# schV2.net
KiCad netlist of a schematic drawn in EAGLE
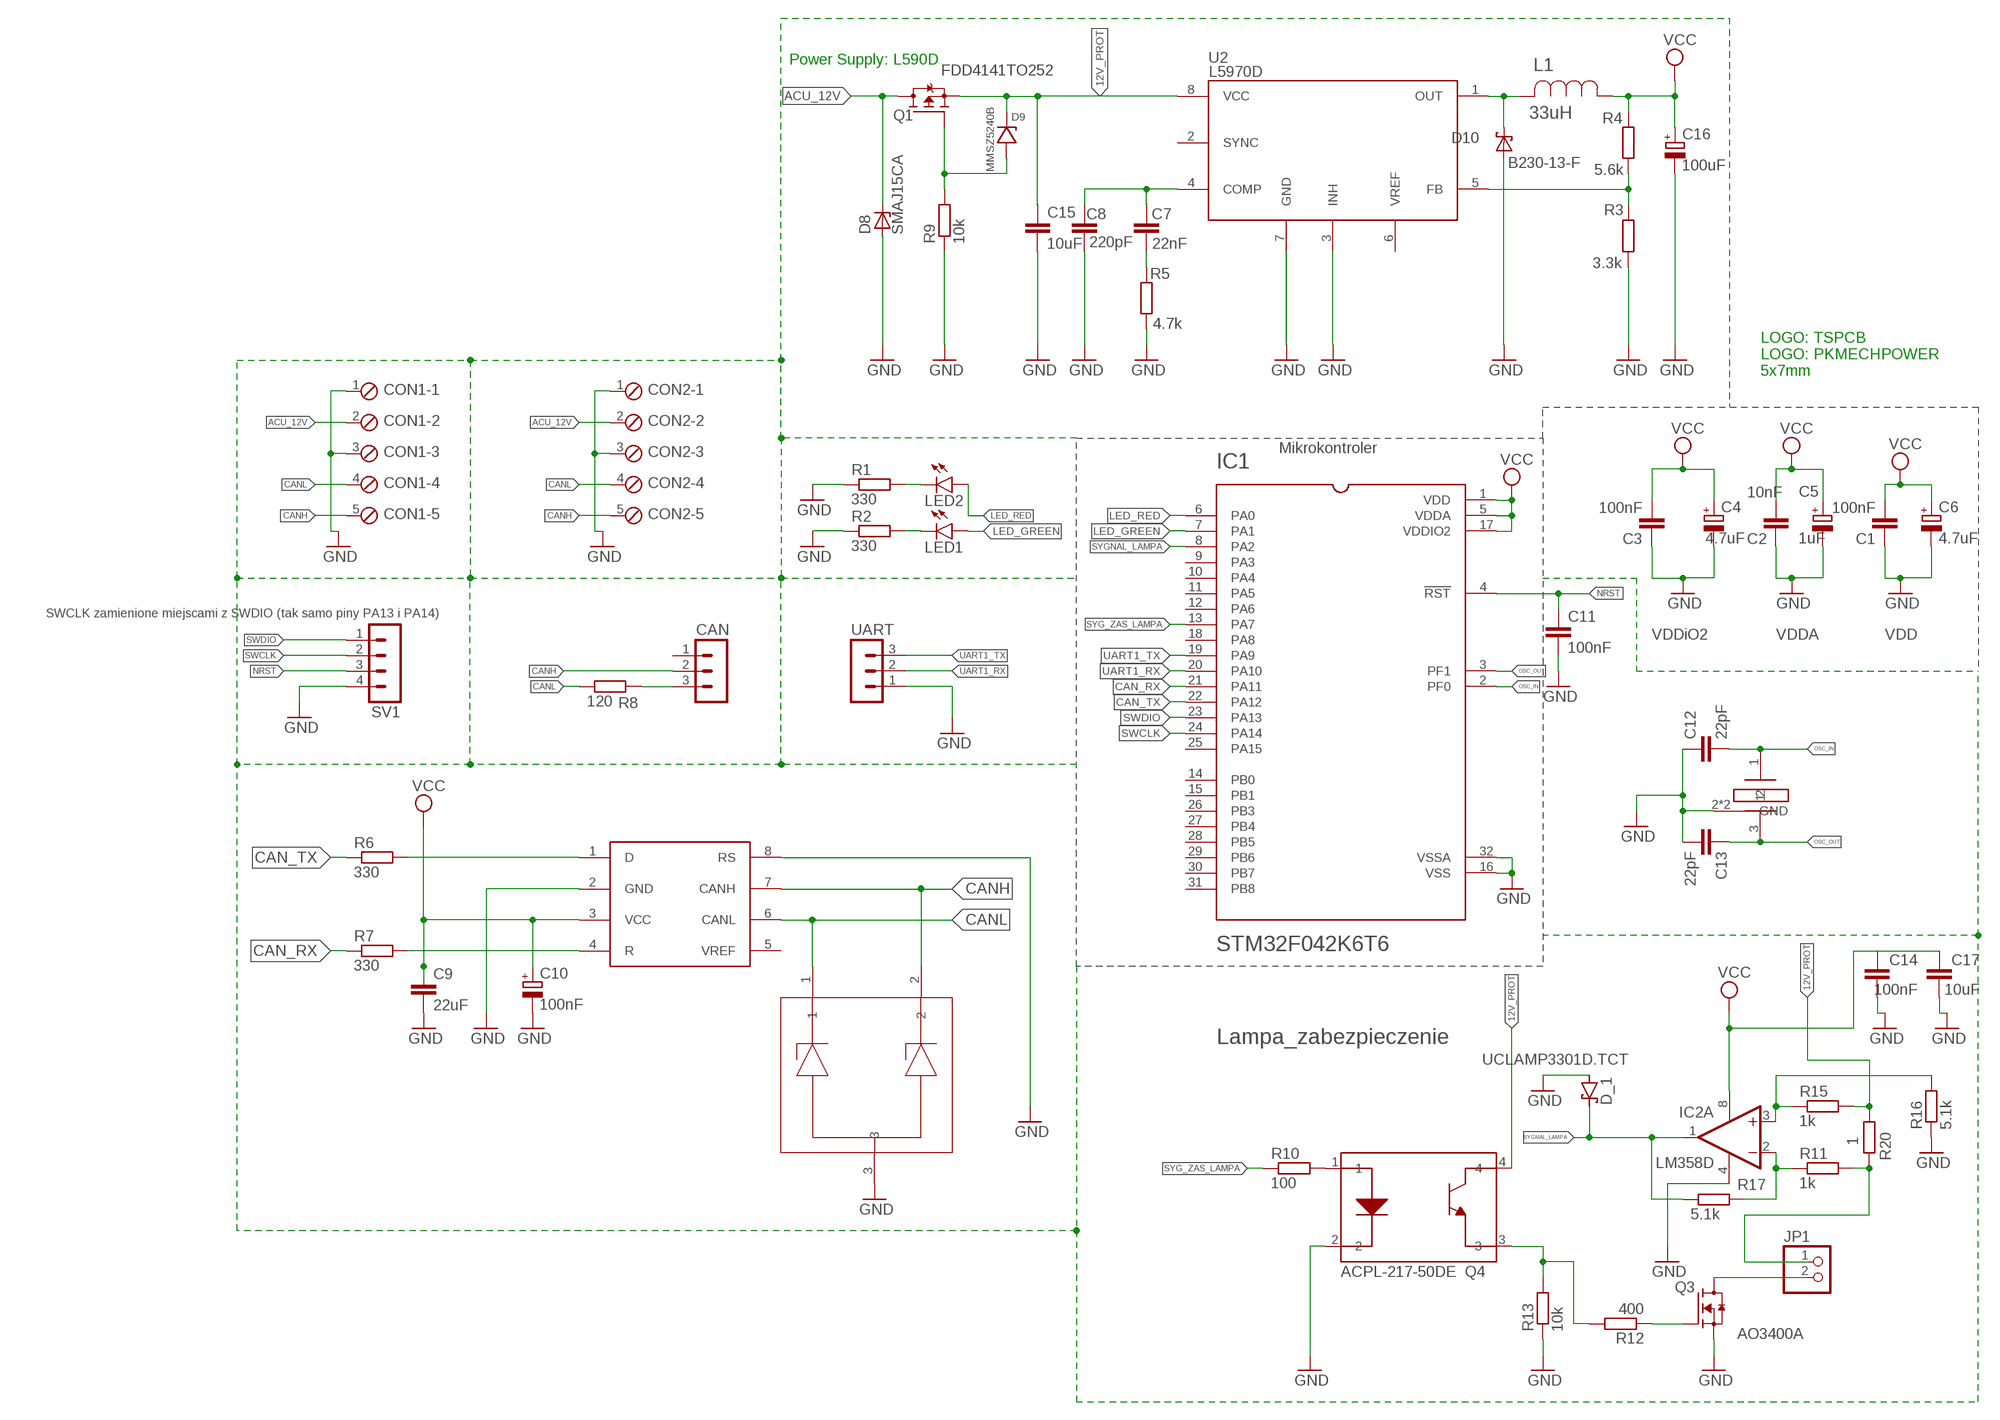
[diagram p0: schematic, sheet 1]

(export (version "E")
  (design (tool "Eeschema 10.0.6"))
  (components
    (comp (ref "C1")
      (value "100nF")
      (footprint "eagle-import:C0805")
      (libsource (lib "eagle-import") (part "C-EUC0805"))
    )
    (comp (ref "C2")
      (value "10nF")
      (footprint "eagle-import:C0805")
      (libsource (lib "eagle-import") (part "C-EUC0805"))
    )
    (comp (ref "C3")
      (value "100nF")
      (footprint "eagle-import:C0805")
      (libsource (lib "eagle-import") (part "C-EUC0805"))
    )
    (comp (ref "C4")
      (value "4.7uF")
      (footprint "eagle-import:SMC_C")
      (libsource (lib "eagle-import") (part "CPOL-EUSMCC"))
    )
    (comp (ref "C5")
      (value "1uF")
      (footprint "eagle-import:SMC_C")
      (libsource (lib "eagle-import") (part "CPOL-EUSMCC"))
    )
    (comp (ref "C6")
      (value "4.7uF")
      (footprint "eagle-import:SMC_C")
      (libsource (lib "eagle-import") (part "CPOL-EUSMCC"))
    )
    (comp (ref "C7")
      (value "22nF")
      (footprint "eagle-import:C0805")
      (libsource (lib "eagle-import") (part "C-EUC0805"))
    )
    (comp (ref "C8")
      (value "220pF")
      (footprint "eagle-import:C0805")
      (libsource (lib "eagle-import") (part "C-EUC0805"))
    )
    (comp (ref "C9")
      (value "22uF")
      (footprint "eagle-import:C0805")
      (libsource (lib "eagle-import") (part "C-EUC0805"))
    )
    (comp (ref "C10")
      (value "100nF")
      (footprint "eagle-import:SMC_C")
      (libsource (lib "eagle-import") (part "CPOL-EUSMCC"))
    )
    (comp (ref "C11")
      (value "100nF")
      (footprint "eagle-import:C0805")
      (libsource (lib "eagle-import") (part "C-EUC0805"))
    )
    (comp (ref "C12")
      (value "22pF")
      (footprint "eagle-import:C0805")
      (libsource (lib "eagle-import") (part "C-EUC0805"))
    )
    (comp (ref "C13")
      (value "22pF")
      (footprint "eagle-import:C0805")
      (libsource (lib "eagle-import") (part "C-EUC0805"))
    )
    (comp (ref "C14")
      (value "100nF")
      (footprint "eagle-import:C0805")
      (libsource (lib "eagle-import") (part "C-EUC0805"))
    )
    (comp (ref "C15")
      (value "10uF")
      (footprint "eagle-import:C1210")
      (libsource (lib "eagle-import") (part "C-EUC1210"))
    )
    (comp (ref "C16")
      (value "100uF")
      (footprint "eagle-import:SMC_D")
      (libsource (lib "eagle-import") (part "CPOL-EUSMCD"))
    )
    (comp (ref "C17")
      (value "10uF")
      (footprint "eagle-import:C0805")
      (libsource (lib "eagle-import") (part "C-EUC0805"))
    )
    (comp (ref "CAN")
      (value "MA03-1")
      (footprint "eagle-import:MA03-1")
      (libsource (lib "eagle-import") (part "MA03-1"))
    )
    (comp (ref "CON1")
      (value "MPT5")
      (footprint "eagle-import:5POL254")
      (libsource (lib "eagle-import") (part "MPT5"))
    )
    (comp (ref "CON2")
      (value "MPT5")
      (footprint "eagle-import:5POL254")
      (libsource (lib "eagle-import") (part "MPT5"))
    )
    (comp (ref "D8")
      (value "SMAJ15CA")
      (footprint "eagle-import:SMA")
      (fields (field (name "MF") "Nexperia USA") (field (name "MP") "PESD5V0X1UB"))
      (libsource (lib "eagle-import") (part "SMAJ15CA"))
    )
    (comp (ref "D9")
      (value "MMSZ5240B")
      (footprint "eagle-import:SOD123")
      (libsource (lib "eagle-import") (part "ZENER_01"))
    )
    (comp (ref "D10")
      (value "B230-13-F")
      (footprint "eagle-import:SMB")
      (libsource (lib "eagle-import") (part "B230-13-F"))
    )
    (comp (ref "D_1")
      (value "UCLAMP3301D.TCT")
      (footprint "eagle-import:SOD323")
      (libsource (lib "eagle-import") (part "UCLAMP3301D.TCT"))
    )
    (comp (ref "IC1")
      (value "STM32F042K6T6")
      (footprint "eagle-import:QFP80P900X900X160-32N")
      (fields (field (name "MF") "STMicroelectronics"))
      (libsource (lib "eagle-import") (part "STM32F042K6T6"))
    )
    (comp (ref "IC2")
      (value "LM358D")
      (footprint "eagle-import:SO08")
      (libsource (lib "eagle-import") (part "LM358D"))
    )
    (comp (ref "JP1")
      (value "PINHD-1X2")
      (footprint "eagle-import:1X02")
      (libsource (lib "eagle-import") (part "PINHD-1X2"))
    )
    (comp (ref "L1")
      (value "33uH")
      (footprint "eagle-import:INDM125125X600N")
      (fields (field (name "MF") "Coilcraft") (field (name "MP") "DR125-680-R"))
      (libsource (lib "eagle-import") (part "DR125-680-R"))
    )
    (comp (ref "LED1")
      (value "LEDCHIP-LED0805")
      (footprint "eagle-import:CHIP-LED0805")
      (libsource (lib "eagle-import") (part "LEDCHIP-LED0805"))
    )
    (comp (ref "LED2")
      (value "LEDCHIP-LED0805")
      (footprint "eagle-import:CHIP-LED0805")
      (libsource (lib "eagle-import") (part "LEDCHIP-LED0805"))
    )
    (comp (ref "Q1")
      (value "FDD4141TO252")
      (footprint "eagle-import:TO252")
      (libsource (lib "eagle-import") (part "FDD4141TO252"))
    )
    (comp (ref "Q3")
      (value "AO3400A")
      (footprint "eagle-import:SOT95P280X125-3N")
      (fields (field (name "MF") "Alpha &"))
      (libsource (lib "eagle-import") (part "AO3400A"))
    )
    (comp (ref "Q4")
      (value "ACPL-217-50DE")
      (footprint "eagle-import:SOIC127P700X220-4N")
      (fields (field (name "MF") "Broadcom / Avago"))
      (libsource (lib "eagle-import") (part "ACPL-217-50DE"))
    )
    (comp (ref "R1")
      (value "330")
      (footprint "eagle-import:R0805")
      (libsource (lib "eagle-import") (part "R-EU_R0805"))
    )
    (comp (ref "R2")
      (value "330")
      (footprint "eagle-import:R0805")
      (libsource (lib "eagle-import") (part "R-EU_R0805"))
    )
    (comp (ref "R3")
      (value "3.3k")
      (footprint "eagle-import:R0805")
      (libsource (lib "eagle-import") (part "R-EU_R0805"))
    )
    (comp (ref "R4")
      (value "5.6k")
      (footprint "eagle-import:R0805")
      (libsource (lib "eagle-import") (part "R-EU_R0805"))
    )
    (comp (ref "R5")
      (value "4.7k")
      (footprint "eagle-import:R0805")
      (libsource (lib "eagle-import") (part "R-EU_R0805"))
    )
    (comp (ref "R6")
      (value "330")
      (footprint "eagle-import:M0805")
      (libsource (lib "eagle-import") (part "R-EU_M0805"))
    )
    (comp (ref "R7")
      (value "330")
      (footprint "eagle-import:M0805")
      (libsource (lib "eagle-import") (part "R-EU_M0805"))
    )
    (comp (ref "R8")
      (value "120")
      (footprint "eagle-import:M0805")
      (libsource (lib "eagle-import") (part "R-EU_M0805"))
    )
    (comp (ref "R9")
      (value "10k")
      (footprint "eagle-import:R0805")
      (libsource (lib "eagle-import") (part "R-EU_R0805"))
    )
    (comp (ref "R10")
      (value "100")
      (footprint "eagle-import:M0805")
      (libsource (lib "eagle-import") (part "R-EU_M0805"))
    )
    (comp (ref "R11")
      (value "1k")
      (footprint "eagle-import:M0805")
      (libsource (lib "eagle-import") (part "R-EU_M0805"))
    )
    (comp (ref "R12")
      (value "400")
      (footprint "eagle-import:M0805")
      (libsource (lib "eagle-import") (part "R-EU_M0805"))
    )
    (comp (ref "R13")
      (value "10k")
      (footprint "eagle-import:M0805")
      (libsource (lib "eagle-import") (part "R-EU_M0805"))
    )
    (comp (ref "R15")
      (value "1k")
      (footprint "eagle-import:M0805")
      (libsource (lib "eagle-import") (part "R-EU_M0805"))
    )
    (comp (ref "R16")
      (value "5.1k")
      (footprint "eagle-import:M0805")
      (libsource (lib "eagle-import") (part "R-EU_M0805"))
    )
    (comp (ref "R17")
      (value "5.1k")
      (footprint "eagle-import:M0805")
      (libsource (lib "eagle-import") (part "R-EU_M0805"))
    )
    (comp (ref "R20")
      (value "1")
      (footprint "eagle-import:R2512")
      (libsource (lib "eagle-import") (part "R-EU_R2512"))
    )
    (comp (ref "SV1")
      (value "MA04-1")
      (footprint "eagle-import:MA04-1")
      (libsource (lib "eagle-import") (part "MA04-1"))
    )
    (comp (ref "U$1")
      (value "SN65HVD")
      (footprint "eagle-import:SO8")
      (libsource (lib "eagle-import") (part "SN65HVD"))
    )
    (comp (ref "U$2")
      (value "PESD3V3S2UT_")
      (footprint "eagle-import:SOT95P230X110-3N")
      (libsource (lib "eagle-import") (part "PESD3V3S2UT_"))
    )
    (comp (ref "U2")
      (value "L5970D")
      (footprint "eagle-import:SO-8")
      (fields (field (name "MF") "STMicroelectronics"))
      (libsource (lib "eagle-import") (part "L5970D"))
    )
    (comp (ref "UART")
      (value "MA03-1")
      (footprint "eagle-import:MA03-1")
      (libsource (lib "eagle-import") (part "MA03-1"))
    )
    (comp (ref "XTAL1")
      (value "CRYSTAL_SMDXT-324")
      (footprint "eagle-import:XT-324")
      (libsource (lib "eagle-import") (part "CRYSTAL_SMDXT-324"))
    )
  )
  (nets
    (net (code "1") (name "12V_PROT") (class "Default")
      (node (ref "C15") (pin "1") (pinfunction "1_1") (pintype "passive"))
      (node (ref "D9") (pin "1") (pinfunction "1_1") (pintype "bidirectional"))
      (node (ref "Q1") (pin "2") (pinfunction "S_2") (pintype "passive"))
      (node (ref "Q4") (pin "4") (pinfunction "4_4") (pintype "passive"))
      (node (ref "R15") (pin "2") (pinfunction "2_2") (pintype "passive"))
      (node (ref "R20") (pin "2") (pinfunction "2_2") (pintype "passive"))
      (node (ref "U2") (pin "8") (pinfunction "VCC_8") (pintype "bidirectional"))
    )
    (net (code "2") (name "ACU_12V") (class "Default")
      (node (ref "CON1") (pin "2") (pinfunction "1_2") (pintype "passive"))
      (node (ref "CON2") (pin "2") (pinfunction "1_2") (pintype "passive"))
      (node (ref "D8") (pin "1") (pinfunction "K_1") (pintype "passive"))
      (node (ref "Q1") (pin "3") (pinfunction "D_3") (pintype "passive"))
    )
    (net (code "3") (name "CANH") (class "Default")
      (node (ref "CAN") (pin "2") (pinfunction "2_2") (pintype "passive"))
      (node (ref "CON1") (pin "5") (pinfunction "1_5") (pintype "passive"))
      (node (ref "CON2") (pin "5") (pinfunction "1_5") (pintype "passive"))
      (node (ref "U$1") (pin "7") (pinfunction "CANH_7") (pintype "bidirectional"))
      (node (ref "U$2") (pin "2") (pinfunction "2_2") (pintype "bidirectional"))
    )
    (net (code "4") (name "CANL") (class "Default")
      (node (ref "CON1") (pin "4") (pinfunction "1_4") (pintype "passive"))
      (node (ref "CON2") (pin "4") (pinfunction "1_4") (pintype "passive"))
      (node (ref "R8") (pin "1") (pinfunction "1_1") (pintype "passive"))
      (node (ref "U$1") (pin "6") (pinfunction "CANL_6") (pintype "bidirectional"))
      (node (ref "U$2") (pin "1") (pinfunction "1_1") (pintype "bidirectional"))
    )
    (net (code "5") (name "CAN_RX") (class "Default")
      (node (ref "IC1") (pin "21") (pinfunction "PA11_21") (pintype "bidirectional"))
      (node (ref "R7") (pin "1") (pinfunction "1_1") (pintype "passive"))
    )
    (net (code "6") (name "CAN_TX") (class "Default")
      (node (ref "IC1") (pin "22") (pinfunction "PA12_22") (pintype "bidirectional"))
      (node (ref "R6") (pin "1") (pinfunction "1_1") (pintype "passive"))
    )
    (net (code "7") (name "GND") (class "Default")
      (node (ref "C1") (pin "1") (pinfunction "1_1") (pintype "passive"))
      (node (ref "C10") (pin "-") (pinfunction "-_-") (pintype "passive"))
      (node (ref "C11") (pin "2") (pinfunction "2_2") (pintype "passive"))
      (node (ref "C12") (pin "1") (pinfunction "1_1") (pintype "passive"))
      (node (ref "C13") (pin "2") (pinfunction "2_2") (pintype "passive"))
      (node (ref "C14") (pin "1") (pinfunction "1_1") (pintype "passive"))
      (node (ref "C15") (pin "2") (pinfunction "2_2") (pintype "passive"))
      (node (ref "C16") (pin "-") (pinfunction "-_-") (pintype "passive"))
      (node (ref "C17") (pin "1") (pinfunction "1_1") (pintype "passive"))
      (node (ref "C2") (pin "1") (pinfunction "1_1") (pintype "passive"))
      (node (ref "C3") (pin "1") (pinfunction "1_1") (pintype "passive"))
      (node (ref "C4") (pin "-") (pinfunction "-_-") (pintype "passive"))
      (node (ref "C5") (pin "-") (pinfunction "-_-") (pintype "passive"))
      (node (ref "C6") (pin "-") (pinfunction "-_-") (pintype "passive"))
      (node (ref "C8") (pin "1") (pinfunction "1_1") (pintype "passive"))
      (node (ref "C9") (pin "2") (pinfunction "2_2") (pintype "passive"))
      (node (ref "CON1") (pin "1") (pinfunction "1_1") (pintype "passive"))
      (node (ref "CON1") (pin "3") (pinfunction "1_3") (pintype "passive"))
      (node (ref "CON2") (pin "1") (pinfunction "1_1") (pintype "passive"))
      (node (ref "CON2") (pin "3") (pinfunction "1_3") (pintype "passive"))
      (node (ref "D10") (pin "2") (pinfunction "A_2") (pintype "passive"))
      (node (ref "D8") (pin "2") (pinfunction "A_2") (pintype "passive"))
      (node (ref "D_1") (pin "1") (pinfunction "A_1") (pintype "passive"))
      (node (ref "IC1") (pin "16") (pinfunction "VSS_16") (pintype "passive"))
      (node (ref "IC1") (pin "32") (pinfunction "VSSA_32") (pintype "passive"))
      (node (ref "IC2") (pin "4") (pinfunction "V-_4") (pintype "power_in"))
      (node (ref "Q3") (pin "2") (pinfunction "S_2") (pintype "passive"))
      (node (ref "Q4") (pin "2") (pinfunction "2_2") (pintype "passive"))
      (node (ref "R1") (pin "1") (pinfunction "1_1") (pintype "passive"))
      (node (ref "R13") (pin "1") (pinfunction "1_1") (pintype "passive"))
      (node (ref "R16") (pin "1") (pinfunction "1_1") (pintype "passive"))
      (node (ref "R2") (pin "1") (pinfunction "1_1") (pintype "passive"))
      (node (ref "R3") (pin "1") (pinfunction "1_1") (pintype "passive"))
      (node (ref "R5") (pin "1") (pinfunction "1_1") (pintype "passive"))
      (node (ref "R9") (pin "1") (pinfunction "1_1") (pintype "passive"))
      (node (ref "SV1") (pin "4") (pinfunction "4_4") (pintype "passive"))
      (node (ref "U$1") (pin "2") (pinfunction "GND_2") (pintype "bidirectional"))
      (node (ref "U$1") (pin "8") (pinfunction "RS_8") (pintype "bidirectional"))
      (node (ref "U$2") (pin "3") (pinfunction "3_3") (pintype "bidirectional"))
      (node (ref "U2") (pin "3") (pinfunction "INH_3") (pintype "bidirectional"))
      (node (ref "U2") (pin "7") (pinfunction "GND_7") (pintype "bidirectional"))
      (node (ref "UART") (pin "1") (pinfunction "1_1") (pintype "passive"))
      (node (ref "XTAL1") (pin "2") (pinfunction "GND_2") (pintype "bidirectional"))
      (node (ref "XTAL1") (pin "4") (pinfunction "GND_4") (pintype "bidirectional"))
    )
    (net (code "8") (name "LED_GREEN") (class "Default")
      (node (ref "IC1") (pin "7") (pinfunction "PA1_7") (pintype "bidirectional"))
      (node (ref "LED1") (pin "A") (pinfunction "A_A") (pintype "passive"))
    )
    (net (code "9") (name "LED_RED") (class "Default")
      (node (ref "IC1") (pin "6") (pinfunction "PA0_6") (pintype "bidirectional"))
      (node (ref "LED2") (pin "A") (pinfunction "A_A") (pintype "passive"))
    )
    (net (code "10") (name "NRST") (class "Default")
      (node (ref "C11") (pin "1") (pinfunction "1_1") (pintype "passive"))
      (node (ref "IC1") (pin "4") (pinfunction "~{RST}_4") (pintype "input"))
      (node (ref "SV1") (pin "3") (pinfunction "3_3") (pintype "passive"))
    )
    (net (code "11") (name "Net-(C7-Pad1)") (class "Default")
      (node (ref "C7") (pin "1") (pinfunction "1_1") (pintype "passive"))
      (node (ref "R5") (pin "2") (pinfunction "2_2") (pintype "passive"))
    )
    (net (code "12") (name "Net-(CAN-Pad3)") (class "Default")
      (node (ref "CAN") (pin "3") (pinfunction "3_3") (pintype "passive"))
      (node (ref "R8") (pin "2") (pinfunction "2_2") (pintype "passive"))
    )
    (net (code "13") (name "Net-(D10-K)") (class "Default")
      (node (ref "D10") (pin "1") (pinfunction "K_1") (pintype "passive"))
      (node (ref "L1") (pin "2") (pinfunction "2_2") (pintype "passive"))
      (node (ref "U2") (pin "1") (pinfunction "OUT_1") (pintype "bidirectional"))
    )
    (net (code "14") (name "Net-(IC2A-+IN)") (class "Default")
      (node (ref "IC2") (pin "3") (pinfunction "+IN_3") (pintype "input"))
      (node (ref "R15") (pin "1") (pinfunction "1_1") (pintype "passive"))
      (node (ref "R16") (pin "2") (pinfunction "2_2") (pintype "passive"))
    )
    (net (code "15") (name "Net-(IC2A--IN)") (class "Default")
      (node (ref "IC2") (pin "2") (pinfunction "-IN_2") (pintype "input"))
      (node (ref "R11") (pin "1") (pinfunction "1_1") (pintype "passive"))
      (node (ref "R17") (pin "2") (pinfunction "2_2") (pintype "passive"))
    )
    (net (code "16") (name "Net-(JP1-Pad1)") (class "Default")
      (node (ref "JP1") (pin "1") (pinfunction "1_1") (pintype "passive"))
      (node (ref "R11") (pin "2") (pinfunction "2_2") (pintype "passive"))
      (node (ref "R20") (pin "1") (pinfunction "1_1") (pintype "passive"))
    )
    (net (code "17") (name "Net-(LED1-PadC)") (class "Default")
      (node (ref "LED1") (pin "C") (pinfunction "C_C") (pintype "passive"))
      (node (ref "R2") (pin "2") (pinfunction "2_2") (pintype "passive"))
    )
    (net (code "18") (name "Net-(LED2-PadC)") (class "Default")
      (node (ref "LED2") (pin "C") (pinfunction "C_C") (pintype "passive"))
      (node (ref "R1") (pin "2") (pinfunction "2_2") (pintype "passive"))
    )
    (net (code "19") (name "Net-(Q1-G)") (class "Default")
      (node (ref "D9") (pin "2") (pinfunction "2_2") (pintype "bidirectional"))
      (node (ref "Q1") (pin "1") (pinfunction "G_1") (pintype "passive"))
      (node (ref "R9") (pin "2") (pinfunction "2_2") (pintype "passive"))
    )
    (net (code "20") (name "Net-(Q3-D)") (class "Default")
      (node (ref "JP1") (pin "2") (pinfunction "2_2") (pintype "passive"))
      (node (ref "Q3") (pin "3") (pinfunction "D_3") (pintype "passive"))
    )
    (net (code "21") (name "Net-(Q3-G)") (class "Default")
      (node (ref "Q3") (pin "1") (pinfunction "G_1") (pintype "passive"))
      (node (ref "R12") (pin "1") (pinfunction "1_1") (pintype "passive"))
    )
    (net (code "22") (name "Net-(Q4-Pad1)") (class "Default")
      (node (ref "Q4") (pin "1") (pinfunction "1_1") (pintype "passive"))
      (node (ref "R10") (pin "2") (pinfunction "2_2") (pintype "passive"))
    )
    (net (code "23") (name "Net-(Q4-Pad3)") (class "Default")
      (node (ref "Q4") (pin "3") (pinfunction "3_3") (pintype "passive"))
      (node (ref "R12") (pin "2") (pinfunction "2_2") (pintype "passive"))
      (node (ref "R13") (pin "2") (pinfunction "2_2") (pintype "passive"))
    )
    (net (code "24") (name "Net-(U$1-D)") (class "Default")
      (node (ref "R6") (pin "2") (pinfunction "2_2") (pintype "passive"))
      (node (ref "U$1") (pin "1") (pinfunction "D_1") (pintype "bidirectional"))
    )
    (net (code "25") (name "Net-(U$1-R)") (class "Default")
      (node (ref "R7") (pin "2") (pinfunction "2_2") (pintype "passive"))
      (node (ref "U$1") (pin "4") (pinfunction "R_4") (pintype "bidirectional"))
    )
    (net (code "26") (name "Net-(U2-COMP)") (class "Default")
      (node (ref "C7") (pin "2") (pinfunction "2_2") (pintype "passive"))
      (node (ref "C8") (pin "2") (pinfunction "2_2") (pintype "passive"))
      (node (ref "U2") (pin "4") (pinfunction "COMP_4") (pintype "bidirectional"))
    )
    (net (code "27") (name "Net-(U2-FB)") (class "Default")
      (node (ref "R3") (pin "2") (pinfunction "2_2") (pintype "passive"))
      (node (ref "R4") (pin "1") (pinfunction "1_1") (pintype "passive"))
      (node (ref "U2") (pin "5") (pinfunction "FB_5") (pintype "bidirectional"))
    )
    (net (code "28") (name "OSC_IN") (class "Default")
      (node (ref "C12") (pin "2") (pinfunction "2_2") (pintype "passive"))
      (node (ref "IC1") (pin "2") (pinfunction "PF0_2") (pintype "bidirectional"))
      (node (ref "XTAL1") (pin "1") (pinfunction "1_1") (pintype "bidirectional"))
    )
    (net (code "29") (name "OSC_OUT") (class "Default")
      (node (ref "C13") (pin "1") (pinfunction "1_1") (pintype "passive"))
      (node (ref "IC1") (pin "3") (pinfunction "PF1_3") (pintype "bidirectional"))
      (node (ref "XTAL1") (pin "3") (pinfunction "2_3") (pintype "bidirectional"))
    )
    (net (code "30") (name "SWCLK") (class "Default")
      (node (ref "IC1") (pin "24") (pinfunction "PA14_24") (pintype "bidirectional"))
      (node (ref "SV1") (pin "2") (pinfunction "2_2") (pintype "passive"))
    )
    (net (code "31") (name "SWDIO") (class "Default")
      (node (ref "IC1") (pin "23") (pinfunction "PA13_23") (pintype "bidirectional"))
      (node (ref "SV1") (pin "1") (pinfunction "1_1") (pintype "passive"))
    )
    (net (code "32") (name "SYGNAL_LAMPA") (class "Default")
      (node (ref "D_1") (pin "2") (pinfunction "C_2") (pintype "passive"))
      (node (ref "IC1") (pin "8") (pinfunction "PA2_8") (pintype "bidirectional"))
      (node (ref "IC2") (pin "1") (pinfunction "OUT_1") (pintype "output"))
      (node (ref "R17") (pin "1") (pinfunction "1_1") (pintype "passive"))
    )
    (net (code "33") (name "SYG_ZAS_LAMPA") (class "Default")
      (node (ref "IC1") (pin "13") (pinfunction "PA7_13") (pintype "bidirectional"))
      (node (ref "R10") (pin "1") (pinfunction "1_1") (pintype "passive"))
    )
    (net (code "34") (name "UART1_RX") (class "Default")
      (node (ref "IC1") (pin "20") (pinfunction "PA10_20") (pintype "bidirectional"))
      (node (ref "UART") (pin "2") (pinfunction "2_2") (pintype "passive"))
    )
    (net (code "35") (name "UART1_TX") (class "Default")
      (node (ref "IC1") (pin "19") (pinfunction "PA9_19") (pintype "bidirectional"))
      (node (ref "UART") (pin "3") (pinfunction "3_3") (pintype "passive"))
    )
    (net (code "36") (name "VCC") (class "Default")
      (node (ref "C1") (pin "2") (pinfunction "2_2") (pintype "passive"))
      (node (ref "C10") (pin "+") (pinfunction "+_+") (pintype "passive"))
      (node (ref "C14") (pin "2") (pinfunction "2_2") (pintype "passive"))
      (node (ref "C16") (pin "+") (pinfunction "+_+") (pintype "passive"))
      (node (ref "C17") (pin "2") (pinfunction "2_2") (pintype "passive"))
      (node (ref "C2") (pin "2") (pinfunction "2_2") (pintype "passive"))
      (node (ref "C3") (pin "2") (pinfunction "2_2") (pintype "passive"))
      (node (ref "C4") (pin "+") (pinfunction "+_+") (pintype "passive"))
      (node (ref "C5") (pin "+") (pinfunction "+_+") (pintype "passive"))
      (node (ref "C6") (pin "+") (pinfunction "+_+") (pintype "passive"))
      (node (ref "C9") (pin "1") (pinfunction "1_1") (pintype "passive"))
      (node (ref "IC1") (pin "1") (pinfunction "VDD_1") (pintype "power_in"))
      (node (ref "IC1") (pin "17") (pinfunction "VDDIO2_17") (pintype "power_in"))
      (node (ref "IC1") (pin "5") (pinfunction "VDDA_5") (pintype "power_in"))
      (node (ref "IC2") (pin "8") (pinfunction "V+_8") (pintype "power_in"))
      (node (ref "L1") (pin "1") (pinfunction "1_1") (pintype "passive"))
      (node (ref "R4") (pin "2") (pinfunction "2_2") (pintype "passive"))
      (node (ref "U$1") (pin "3") (pinfunction "VCC_3") (pintype "bidirectional"))
    )
    (net (code "37") (name "unconnected-(CAN-Pad1)") (class "Default")
      (node (ref "CAN") (pin "1") (pinfunction "1_1") (pintype "passive"))
    )
    (net (code "38") (name "unconnected-(IC1-PA3-Pad9)") (class "Default")
      (node (ref "IC1") (pin "9") (pinfunction "PA3_9") (pintype "bidirectional"))
    )
    (net (code "39") (name "unconnected-(IC1-PA4-Pad10)") (class "Default")
      (node (ref "IC1") (pin "10") (pinfunction "PA4_10") (pintype "bidirectional"))
    )
    (net (code "40") (name "unconnected-(IC1-PA5-Pad11)") (class "Default")
      (node (ref "IC1") (pin "11") (pinfunction "PA5_11") (pintype "bidirectional"))
    )
    (net (code "41") (name "unconnected-(IC1-PA6-Pad12)") (class "Default")
      (node (ref "IC1") (pin "12") (pinfunction "PA6_12") (pintype "bidirectional"))
    )
    (net (code "42") (name "unconnected-(IC1-PA8-Pad18)") (class "Default")
      (node (ref "IC1") (pin "18") (pinfunction "PA8_18") (pintype "bidirectional"))
    )
    (net (code "43") (name "unconnected-(IC1-PA15-Pad25)") (class "Default")
      (node (ref "IC1") (pin "25") (pinfunction "PA15_25") (pintype "bidirectional"))
    )
    (net (code "44") (name "unconnected-(IC1-PB0-Pad14)") (class "Default")
      (node (ref "IC1") (pin "14") (pinfunction "PB0_14") (pintype "bidirectional"))
    )
    (net (code "45") (name "unconnected-(IC1-PB1-Pad15)") (class "Default")
      (node (ref "IC1") (pin "15") (pinfunction "PB1_15") (pintype "bidirectional"))
    )
    (net (code "46") (name "unconnected-(IC1-PB3-Pad26)") (class "Default")
      (node (ref "IC1") (pin "26") (pinfunction "PB3_26") (pintype "bidirectional"))
    )
    (net (code "47") (name "unconnected-(IC1-PB4-Pad27)") (class "Default")
      (node (ref "IC1") (pin "27") (pinfunction "PB4_27") (pintype "bidirectional"))
    )
    (net (code "48") (name "unconnected-(IC1-PB5-Pad28)") (class "Default")
      (node (ref "IC1") (pin "28") (pinfunction "PB5_28") (pintype "bidirectional"))
    )
    (net (code "49") (name "unconnected-(IC1-PB6-Pad29)") (class "Default")
      (node (ref "IC1") (pin "29") (pinfunction "PB6_29") (pintype "bidirectional"))
    )
    (net (code "50") (name "unconnected-(IC1-PB7-Pad30)") (class "Default")
      (node (ref "IC1") (pin "30") (pinfunction "PB7_30") (pintype "bidirectional"))
    )
    (net (code "51") (name "unconnected-(IC1-PB8-Pad31)") (class "Default")
      (node (ref "IC1") (pin "31") (pinfunction "PB8_31") (pintype "bidirectional"))
    )
    (net (code "52") (name "unconnected-(U$1-VREF-Pad5)") (class "Default")
      (node (ref "U$1") (pin "5") (pinfunction "VREF_5") (pintype "bidirectional"))
    )
    (net (code "53") (name "unconnected-(U2-SYNC-Pad2)") (class "Default")
      (node (ref "U2") (pin "2") (pinfunction "SYNC_2") (pintype "bidirectional"))
    )
    (net (code "54") (name "unconnected-(U2-VREF-Pad6)") (class "Default")
      (node (ref "U2") (pin "6") (pinfunction "VREF_6") (pintype "bidirectional"))
    )
  )
)
